# sensorboard_14_v7.net
KiCad netlist of a schematic drawn in EAGLE
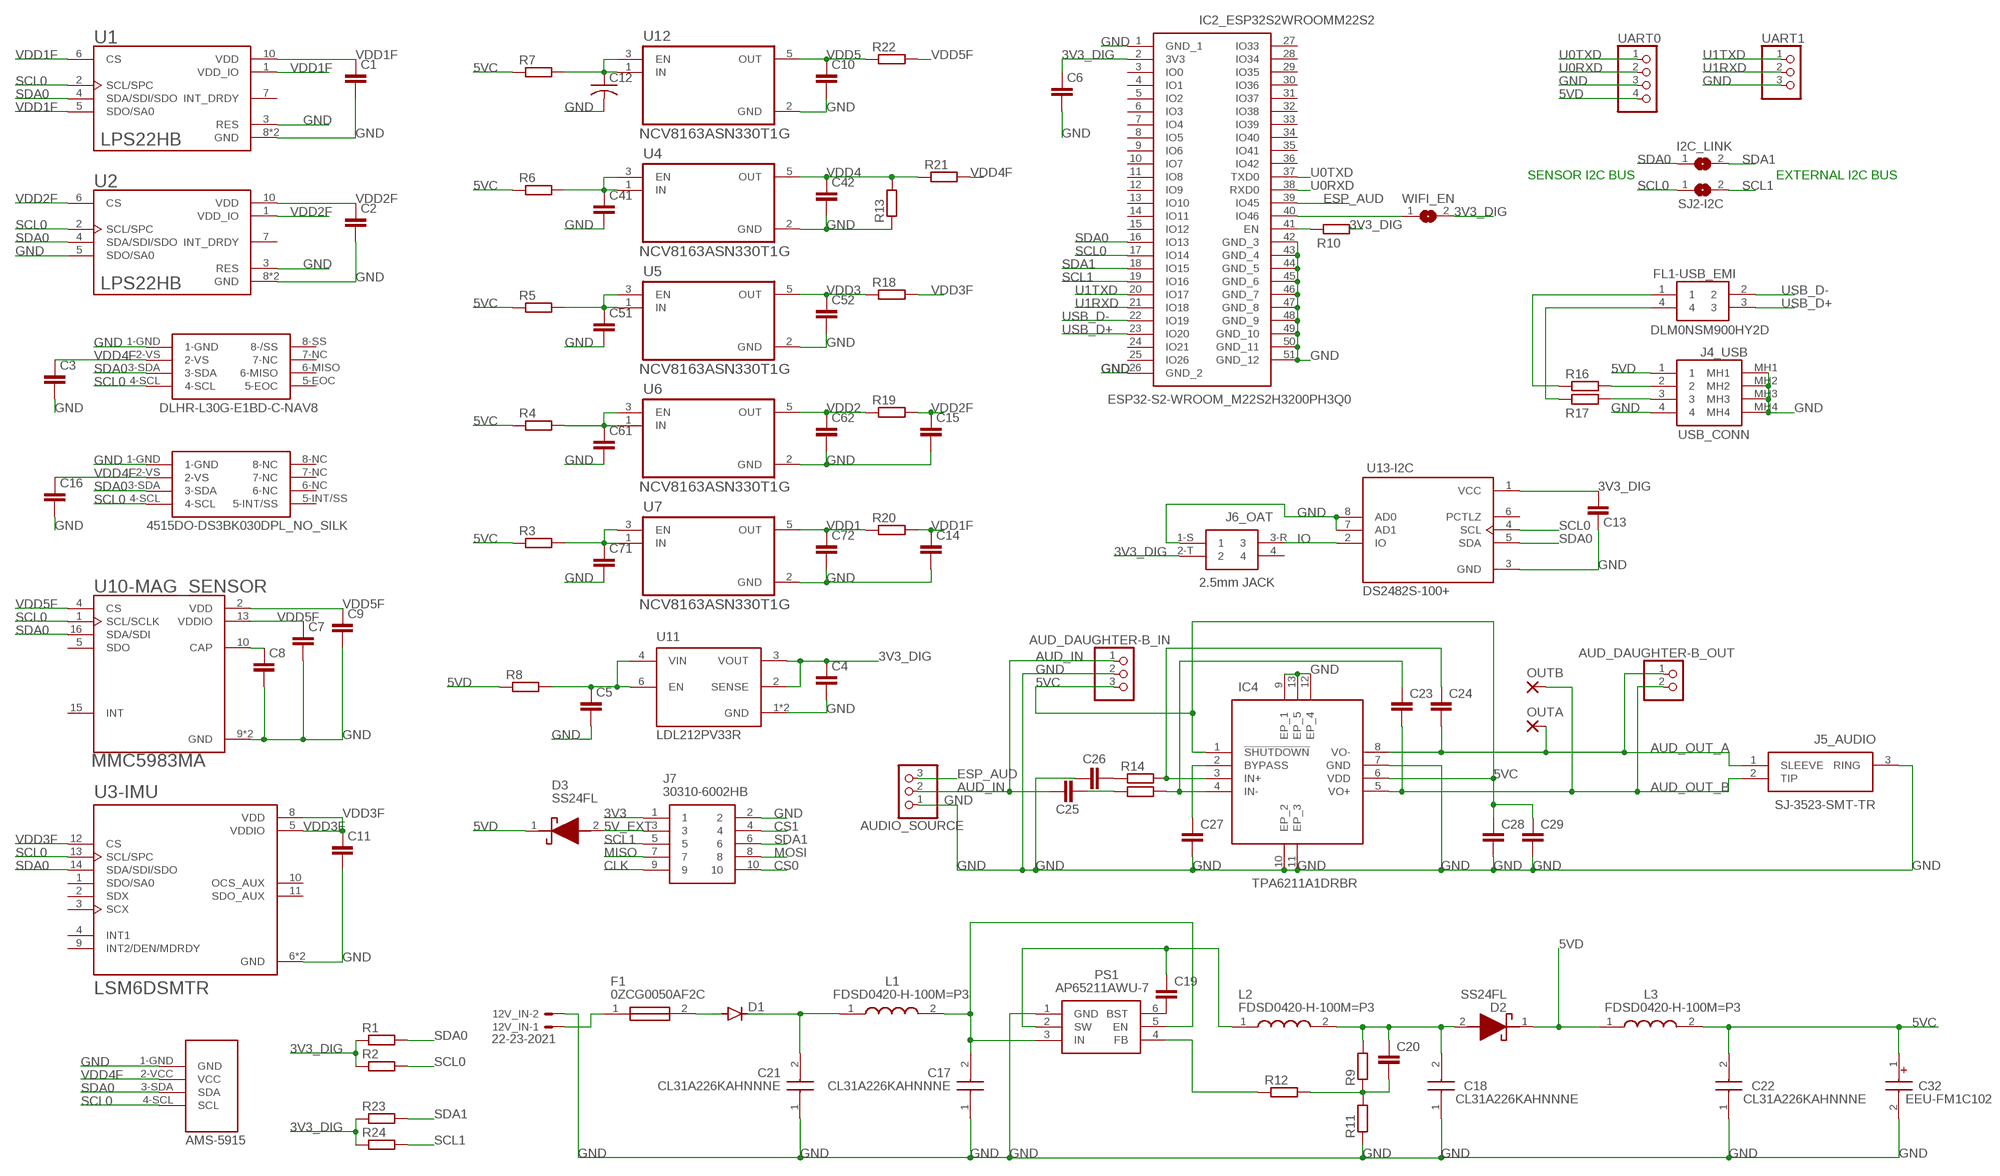
[diagram p0: schematic, sheet 1]

(export (version "E")
  (design (tool "Eeschema 10.0.6"))
  (components
    (comp (ref "12V_IN")
      (value "22-23-2021")
      (footprint "eagle-import:22-23-2021")
      (fields (field (name "MF") "MOLEX"))
      (libsource (lib "eagle-import") (part "22-23-2021"))
    )
    (comp (ref "AUDIO_SOURCE")
      (value "PINHD-1X3")
      (footprint "eagle-import:1X03")
      (libsource (lib "eagle-import") (part "PINHD-1X3"))
    )
    (comp (ref "AUD_DAUGHTER-B_IN")
      (value "PINHD-1X3")
      (footprint "eagle-import:1X03")
      (libsource (lib "eagle-import") (part "PINHD-1X3"))
    )
    (comp (ref "AUD_DAUGHTER-B_OUT")
      (value "PINHD-1X2")
      (footprint "eagle-import:1X02")
      (libsource (lib "eagle-import") (part "PINHD-1X2"))
    )
    (comp (ref "C1")
      (value "C-EUC0603")
      (footprint "eagle-import:C0603")
      (libsource (lib "eagle-import") (part "C-EUC0603"))
    )
    (comp (ref "C2")
      (value "C-EUC0603")
      (footprint "eagle-import:C0603")
      (libsource (lib "eagle-import") (part "C-EUC0603"))
    )
    (comp (ref "C3")
      (value "C-EUC0805")
      (footprint "eagle-import:C0805")
      (libsource (lib "eagle-import") (part "C-EUC0805"))
    )
    (comp (ref "C4")
      (value "C-EUC0805")
      (footprint "eagle-import:C0805")
      (libsource (lib "eagle-import") (part "C-EUC0805"))
    )
    (comp (ref "C5")
      (value "C-EUC0805")
      (footprint "eagle-import:C0805")
      (libsource (lib "eagle-import") (part "C-EUC0805"))
    )
    (comp (ref "C6")
      (value "C-EUC0805")
      (footprint "eagle-import:C0805")
      (libsource (lib "eagle-import") (part "C-EUC0805"))
    )
    (comp (ref "C7")
      (value "C-EUC0805")
      (footprint "eagle-import:C0805")
      (libsource (lib "eagle-import") (part "C-EUC0805"))
    )
    (comp (ref "C8")
      (value "C-EUC0805")
      (footprint "eagle-import:C0805")
      (libsource (lib "eagle-import") (part "C-EUC0805"))
    )
    (comp (ref "C9")
      (value "C-EUC0805")
      (footprint "eagle-import:C0805")
      (libsource (lib "eagle-import") (part "C-EUC0805"))
    )
    (comp (ref "C10")
      (value "C-EUC0805")
      (footprint "eagle-import:C0805")
      (libsource (lib "eagle-import") (part "C-EUC0805"))
    )
    (comp (ref "C11")
      (value "C-EUC0805")
      (footprint "eagle-import:C0805")
      (libsource (lib "eagle-import") (part "C-EUC0805"))
    )
    (comp (ref "C12")
      (value "C-USC0805")
      (footprint "eagle-import:C0805")
      (libsource (lib "eagle-import") (part "C-USC0805"))
    )
    (comp (ref "C13")
      (value "C-EUC0805")
      (footprint "eagle-import:C0805")
      (libsource (lib "eagle-import") (part "C-EUC0805"))
    )
    (comp (ref "C14")
      (value "C-EUC0805")
      (footprint "eagle-import:C0805")
      (libsource (lib "eagle-import") (part "C-EUC0805"))
    )
    (comp (ref "C15")
      (value "C-EUC0805")
      (footprint "eagle-import:C0805")
      (libsource (lib "eagle-import") (part "C-EUC0805"))
    )
    (comp (ref "C16")
      (value "C-EUC0805")
      (footprint "eagle-import:C0805")
      (libsource (lib "eagle-import") (part "C-EUC0805"))
    )
    (comp (ref "C17")
      (value "CL31A226KAHNNNE")
      (footprint "eagle-import:CAPC3216X180N")
      (libsource (lib "eagle-import") (part "CL31A226KAHNNNE"))
    )
    (comp (ref "C18")
      (value "CL31A226KAHNNNE")
      (footprint "eagle-import:CAPC3216X180N")
      (libsource (lib "eagle-import") (part "CL31A226KAHNNNE"))
    )
    (comp (ref "C19")
      (value "C-EUC0805")
      (footprint "eagle-import:C0805")
      (libsource (lib "eagle-import") (part "C-EUC0805"))
    )
    (comp (ref "C20")
      (value "C-EUC0805")
      (footprint "eagle-import:C0805")
      (libsource (lib "eagle-import") (part "C-EUC0805"))
    )
    (comp (ref "C21")
      (value "CL31A226KAHNNNE")
      (footprint "eagle-import:CAPC3216X180N")
      (libsource (lib "eagle-import") (part "CL31A226KAHNNNE"))
    )
    (comp (ref "C22")
      (value "CL31A226KAHNNNE")
      (footprint "eagle-import:CAPC3216X180N")
      (libsource (lib "eagle-import") (part "CL31A226KAHNNNE"))
    )
    (comp (ref "C23")
      (value "C-EUC0805")
      (footprint "eagle-import:C0805")
      (libsource (lib "eagle-import") (part "C-EUC0805"))
    )
    (comp (ref "C24")
      (value "C-EUC0805")
      (footprint "eagle-import:C0805")
      (libsource (lib "eagle-import") (part "C-EUC0805"))
    )
    (comp (ref "C25")
      (value "C-EUC1206")
      (footprint "eagle-import:C1206")
      (libsource (lib "eagle-import") (part "C-EUC1206"))
    )
    (comp (ref "C26")
      (value "C-EUC1206")
      (footprint "eagle-import:C1206")
      (libsource (lib "eagle-import") (part "C-EUC1206"))
    )
    (comp (ref "C27")
      (value "C-EUC1206")
      (footprint "eagle-import:C1206")
      (libsource (lib "eagle-import") (part "C-EUC1206"))
    )
    (comp (ref "C28")
      (value "C-EUC1206")
      (footprint "eagle-import:C1206")
      (libsource (lib "eagle-import") (part "C-EUC1206"))
    )
    (comp (ref "C29")
      (value "C-EUC1206")
      (footprint "eagle-import:C1206")
      (libsource (lib "eagle-import") (part "C-EUC1206"))
    )
    (comp (ref "C32")
      (value "EEU-FM1C102")
      (footprint "eagle-import:CAPPRD500W65D1000H2200")
      (fields (field (name "MOUSER_PART_NUMBER") "667-EEU-FM1C102"))
      (libsource (lib "eagle-import") (part "EEU-FM1C102"))
    )
    (comp (ref "C41")
      (value "C-EUC0805")
      (footprint "eagle-import:C0805")
      (libsource (lib "eagle-import") (part "C-EUC0805"))
    )
    (comp (ref "C42")
      (value "C-EUC0805")
      (footprint "eagle-import:C0805")
      (libsource (lib "eagle-import") (part "C-EUC0805"))
    )
    (comp (ref "C51")
      (value "C-EUC0805")
      (footprint "eagle-import:C0805")
      (libsource (lib "eagle-import") (part "C-EUC0805"))
    )
    (comp (ref "C52")
      (value "C-EUC0805")
      (footprint "eagle-import:C0805")
      (libsource (lib "eagle-import") (part "C-EUC0805"))
    )
    (comp (ref "C61")
      (value "C-EUC0805")
      (footprint "eagle-import:C0805")
      (libsource (lib "eagle-import") (part "C-EUC0805"))
    )
    (comp (ref "C62")
      (value "C-EUC0805")
      (footprint "eagle-import:C0805")
      (libsource (lib "eagle-import") (part "C-EUC0805"))
    )
    (comp (ref "C71")
      (value "C-EUC0805")
      (footprint "eagle-import:C0805")
      (libsource (lib "eagle-import") (part "C-EUC0805"))
    )
    (comp (ref "C72")
      (value "C-EUC0805")
      (footprint "eagle-import:C0805")
      (libsource (lib "eagle-import") (part "C-EUC0805"))
    )
    (comp (ref "D1")
      (value "DIODE-DO-214AC")
      (footprint "eagle-import:DO-214AC")
      (libsource (lib "eagle-import") (part "DIODE-DO-214AC"))
    )
    (comp (ref "D2")
      (value "SS24FL")
      (footprint "eagle-import:SODFL3617X108N")
      (fields (field (name "MOUSER_PART_NUMBER") "512-SS24FL"))
      (libsource (lib "eagle-import") (part "SS24FL"))
    )
    (comp (ref "D3")
      (value "SS24FL")
      (footprint "eagle-import:SODFL3617X108N")
      (fields (field (name "MOUSER_PART_NUMBER") "512-SS24FL"))
      (libsource (lib "eagle-import") (part "SS24FL"))
    )
    (comp (ref "DLHR-L30G-E1BD-C-NAV8")
      (value "DLHR-L30G-E1BD-C-NAV8")
      (footprint "eagle-import:DLHR-L30G-E1BD-C-NAV8")
      (libsource (lib "eagle-import") (part "DLHR-L30G-E1BD-C-NAV8"))
    )
    (comp (ref "F1")
      (value "0ZCG0050AF2C")
      (footprint "eagle-import:FUSC4632X75N")
      (fields (field (name "MOUSER_PART_NUMBER") "530-0ZCG0050AF2C"))
      (libsource (lib "eagle-import") (part "0ZCG0050AF2C"))
    )
    (comp (ref "FL1-USB_EMI")
      (value "DLM0NSM900HY2D")
      (footprint "eagle-import:DLM0NSB120HY2B")
      (fields (field (name "MOUSER_PART_NUMBER") "81-DLM0NSM900HY2D"))
      (libsource (lib "eagle-import") (part "DLM0NSM900HY2D"))
    )
    (comp (ref "I2C_LINK")
      (value "SJ")
      (footprint "eagle-import:SJ")
      (libsource (lib "eagle-import") (part "SJ"))
    )
    (comp (ref "IC2_ESP32S2WROOMM22S2")
      (value "ESP32-S2-WROOM_M22S2H3200PH3Q0")
      (footprint "eagle-import:ESP32S2WROOMM22S2H3200PH3Q0")
      (fields
        (field (name "MANUFACTURER_PART_NUMBER") "ESP32-S2-WROOM(M22S2H3200PH3Q0)")
        (field (name "MOUSER_PART_NUMBER") "356-ESP32S2WRM3200PH")
      )
      (libsource (lib "eagle-import") (part "ESP32-S2-WROOM_M22S2H3200PH3Q0"))
    )
    (comp (ref "IC4")
      (value "TPA6211A1DRBR")
      (footprint "eagle-import:TPS7A8033DRBT")
      (fields (field (name "MOUSER_PART_NUMBER") "595-TPA6211A1DRBR"))
      (libsource (lib "eagle-import") (part "TPA6211A1DRBR"))
    )
    (comp (ref "J4_USB")
      (value "USB_CONN")
      (footprint "eagle-import:737250110BLF")
      (fields
        (field (name "MANUFACTURER_PART_NUMBER") "73725-0110BLF")
        (field (name "MOUSER_PART_NUMBER") "649-73725-0110BLF")
      )
      (libsource (lib "eagle-import") (part "73725-0110BLF"))
    )
    (comp (ref "J5_AUDIO")
      (value "SJ-3523-SMT-TR")
      (footprint "eagle-import:SJ3523SMTTR")
      (fields (field (name "MOUSER_PART_NUMBER") "490-SJ-3523-SMT-TR"))
      (libsource (lib "eagle-import") (part "SJ-3523-SMT-TR"))
    )
    (comp (ref "J6_OAT")
      (value "2.5mm JACK")
      (footprint "eagle-import:SJ-2523-SMT-TR")
      (fields
        (field (name "MANUFACTURER_PART_NUMBER") "SJ-2523-SMT-TR")
        (field (name "MOUSER_PART_NUMBER") "490-SJ-2523-SMT-TR")
      )
      (libsource (lib "eagle-import") (part "SJ-2523-SMT-TR"))
    )
    (comp (ref "J7")
      (value "30310-6002HB")
      (footprint "eagle-import:SHDR10W64P254_2X5_2030X878X930")
      (fields (field (name "MOUSER_PART_NUMBER") "517-30310-6002"))
      (libsource (lib "eagle-import") (part "30310-6002HB"))
    )
    (comp (ref "L1")
      (value "FDSD0420-H-100M=P3")
      (footprint "eagle-import:FDSD0420WH150MP3")
      (fields (field (name "MOUSER_PART_NUMBER") "81-FDSD0420-H-100MP3"))
      (libsource (lib "eagle-import") (part "FDSD0420-H-100M=P3"))
    )
    (comp (ref "L2")
      (value "FDSD0420-H-100M=P3")
      (footprint "eagle-import:FDSD0420WH150MP3")
      (fields (field (name "MOUSER_PART_NUMBER") "81-FDSD0420-H-100MP3"))
      (libsource (lib "eagle-import") (part "FDSD0420-H-100M=P3"))
    )
    (comp (ref "L3")
      (value "FDSD0420-H-100M=P3")
      (footprint "eagle-import:FDSD0420WH150MP3")
      (fields (field (name "MOUSER_PART_NUMBER") "81-FDSD0420-H-100MP3"))
      (libsource (lib "eagle-import") (part "FDSD0420-H-100M=P3"))
    )
    (comp (ref "OUTA")
      (value "SMD2_SMALLSMALL")
      (footprint "eagle-import:SMD2_SMALL")
      (libsource (lib "eagle-import") (part "SMD2_SMALLSMALL"))
    )
    (comp (ref "OUTB")
      (value "SMD2_SMALLSMALL")
      (footprint "eagle-import:SMD2_SMALL")
      (libsource (lib "eagle-import") (part "SMD2_SMALLSMALL"))
    )
    (comp (ref "PS1")
      (value "AP65211AWU-7")
      (footprint "eagle-import:SOT95P280X90-6N")
      (fields (field (name "MOUSER_PART_NUMBER") "621-AP65211AWU-7"))
      (libsource (lib "eagle-import") (part "AP65211AWU-7"))
    )
    (comp (ref "R1")
      (value "R-EU_R0805")
      (footprint "eagle-import:R0805")
      (libsource (lib "eagle-import") (part "R-EU_R0805"))
    )
    (comp (ref "R2")
      (value "R-EU_R0805")
      (footprint "eagle-import:R0805")
      (libsource (lib "eagle-import") (part "R-EU_R0805"))
    )
    (comp (ref "R3")
      (value "R-EU_R0805")
      (footprint "eagle-import:R0805")
      (libsource (lib "eagle-import") (part "R-EU_R0805"))
    )
    (comp (ref "R4")
      (value "R-EU_R0805")
      (footprint "eagle-import:R0805")
      (libsource (lib "eagle-import") (part "R-EU_R0805"))
    )
    (comp (ref "R5")
      (value "R-EU_R0805")
      (footprint "eagle-import:R0805")
      (libsource (lib "eagle-import") (part "R-EU_R0805"))
    )
    (comp (ref "R6")
      (value "R-EU_R0805")
      (footprint "eagle-import:R0805")
      (libsource (lib "eagle-import") (part "R-EU_R0805"))
    )
    (comp (ref "R7")
      (value "R-EU_R0805")
      (footprint "eagle-import:R0805")
      (libsource (lib "eagle-import") (part "R-EU_R0805"))
    )
    (comp (ref "R8")
      (value "R-EU_R0805")
      (footprint "eagle-import:R0805")
      (libsource (lib "eagle-import") (part "R-EU_R0805"))
    )
    (comp (ref "R9")
      (value "R-EU_R0805")
      (footprint "eagle-import:R0805")
      (libsource (lib "eagle-import") (part "R-EU_R0805"))
    )
    (comp (ref "R10")
      (value "R-EU_R0805")
      (footprint "eagle-import:R0805")
      (libsource (lib "eagle-import") (part "R-EU_R0805"))
    )
    (comp (ref "R11")
      (value "R-EU_R0805")
      (footprint "eagle-import:R0805")
      (libsource (lib "eagle-import") (part "R-EU_R0805"))
    )
    (comp (ref "R12")
      (value "R-EU_R0805")
      (footprint "eagle-import:R0805")
      (libsource (lib "eagle-import") (part "R-EU_R0805"))
    )
    (comp (ref "R13")
      (value "R-EU_R0805")
      (footprint "eagle-import:R0805")
      (libsource (lib "eagle-import") (part "R-EU_R0805"))
    )
    (comp (ref "R14")
      (value "R-EU_R0805")
      (footprint "eagle-import:R0805")
      (libsource (lib "eagle-import") (part "R-EU_R0805"))
    )
    (comp (ref "R15")
      (value "R-EU_R0805")
      (footprint "eagle-import:R0805")
      (libsource (lib "eagle-import") (part "R-EU_R0805"))
    )
    (comp (ref "R16")
      (value "R-EU_R0805")
      (footprint "eagle-import:R0805")
      (libsource (lib "eagle-import") (part "R-EU_R0805"))
    )
    (comp (ref "R17")
      (value "R-EU_R0805")
      (footprint "eagle-import:R0805")
      (libsource (lib "eagle-import") (part "R-EU_R0805"))
    )
    (comp (ref "R18")
      (value "R-EU_R0805")
      (footprint "eagle-import:R0805")
      (libsource (lib "eagle-import") (part "R-EU_R0805"))
    )
    (comp (ref "R19")
      (value "R-EU_R0805")
      (footprint "eagle-import:R0805")
      (libsource (lib "eagle-import") (part "R-EU_R0805"))
    )
    (comp (ref "R20")
      (value "R-EU_R0805")
      (footprint "eagle-import:R0805")
      (libsource (lib "eagle-import") (part "R-EU_R0805"))
    )
    (comp (ref "R21")
      (value "R-EU_R0805")
      (footprint "eagle-import:R0805")
      (libsource (lib "eagle-import") (part "R-EU_R0805"))
    )
    (comp (ref "R22")
      (value "R-EU_R0805")
      (footprint "eagle-import:R0805")
      (libsource (lib "eagle-import") (part "R-EU_R0805"))
    )
    (comp (ref "R23")
      (value "R-EU_R0805")
      (footprint "eagle-import:R0805")
      (libsource (lib "eagle-import") (part "R-EU_R0805"))
    )
    (comp (ref "R24")
      (value "R-EU_R0805")
      (footprint "eagle-import:R0805")
      (libsource (lib "eagle-import") (part "R-EU_R0805"))
    )
    (comp (ref "SJ2-I2C")
      (value "SJ")
      (footprint "eagle-import:SJ")
      (libsource (lib "eagle-import") (part "SJ"))
    )
    (comp (ref "U$1")
      (value "AMS-5915")
      (footprint "eagle-import:AMS-5915")
      (libsource (lib "eagle-import") (part "AMS-5915"))
    )
    (comp (ref "U$4")
      (value "4515DO-DS3BK030DPL_NO_SILKNO_SILK")
      (footprint "eagle-import:4515DO-DS3BK030DPL_NO_SILK")
      (libsource (lib "eagle-import") (part "4515DO-DS3BK030DPL_NO_SILKNO_SILK"))
    )
    (comp (ref "U1")
      (value "LPS22HB")
      (footprint "eagle-import:LGA10R50P2X3_200X200X80")
      (fields (field (name "MF") "STMicroelectronics"))
      (libsource (lib "eagle-import") (part "LPS22HB"))
    )
    (comp (ref "U2")
      (value "LPS22HB")
      (footprint "eagle-import:LGA10R50P2X3_200X200X80")
      (fields (field (name "MF") "STMicroelectronics"))
      (libsource (lib "eagle-import") (part "LPS22HB"))
    )
    (comp (ref "U3-IMU")
      (value "LSM6DSMTR")
      (footprint "eagle-import:PQFN50P300X250X86-14N")
      (fields (field (name "MF") "STMicroelectronics"))
      (libsource (lib "eagle-import") (part "LSM6DSMTR"))
    )
    (comp (ref "U4")
      (value "NCV8163ASN330T1G")
      (footprint "eagle-import:SOP95P275X110-5N")
      (fields (field (name "MF") "ON Semiconductor"))
      (libsource (lib "eagle-import") (part "NCV8163ASN330T1G"))
    )
    (comp (ref "U5")
      (value "NCV8163ASN330T1G")
      (footprint "eagle-import:SOP95P275X110-5N")
      (fields (field (name "MF") "ON Semiconductor"))
      (libsource (lib "eagle-import") (part "NCV8163ASN330T1G"))
    )
    (comp (ref "U6")
      (value "NCV8163ASN330T1G")
      (footprint "eagle-import:SOP95P275X110-5N")
      (fields (field (name "MF") "ON Semiconductor"))
      (libsource (lib "eagle-import") (part "NCV8163ASN330T1G"))
    )
    (comp (ref "U7")
      (value "NCV8163ASN330T1G")
      (footprint "eagle-import:SOP95P275X110-5N")
      (fields (field (name "MF") "ON Semiconductor"))
      (libsource (lib "eagle-import") (part "NCV8163ASN330T1G"))
    )
    (comp (ref "U10-MAG_SENSOR")
      (value "MMC5983MA")
      (footprint "eagle-import:LGA16R50P4X4_330X330X100")
      (fields (field (name "MF") "ON Semiconductor") (field (name "MP") "FIS1100"))
      (libsource (lib "eagle-import") (part "MMC5983MA"))
    )
    (comp (ref "U11")
      (value "LDL212PV33R")
      (footprint "eagle-import:SON50P200X200X80-7N")
      (fields (field (name "MF") "STMicroelectronics"))
      (libsource (lib "eagle-import") (part "LDL212PV33R"))
    )
    (comp (ref "U12")
      (value "NCV8163ASN330T1G")
      (footprint "eagle-import:SOP95P275X110-5N")
      (fields (field (name "MF") "ON Semiconductor"))
      (libsource (lib "eagle-import") (part "NCV8163ASN330T1G"))
    )
    (comp (ref "U13-I2C")
      (value "DS2482S-100+")
      (footprint "eagle-import:SOIC127P600X175-8N")
      (fields (field (name "MF") "Maxim Integrated"))
      (libsource (lib "eagle-import") (part "DS2482S-100+"))
    )
    (comp (ref "UART0")
      (value "PINHD-1X4")
      (footprint "eagle-import:1X04")
      (libsource (lib "eagle-import") (part "PINHD-1X4"))
    )
    (comp (ref "UART1")
      (value "PINHD-1X3")
      (footprint "eagle-import:1X03")
      (libsource (lib "eagle-import") (part "PINHD-1X3"))
    )
    (comp (ref "WIFI_EN")
      (value "SJ")
      (footprint "eagle-import:SJ")
      (libsource (lib "eagle-import") (part "SJ"))
    )
  )
  (nets
    (net (code "1") (name "/3V3") (class "Default")
      (node (ref "J7") (pin "1") (pinfunction "1_1") (pintype "bidirectional"))
    )
    (net (code "2") (name "/3V3_DIG") (class "Default")
      (node (ref "C13") (pin "1") (pinfunction "1_1") (pintype "passive"))
      (node (ref "C4") (pin "1") (pinfunction "1_1") (pintype "passive"))
      (node (ref "C6") (pin "1") (pinfunction "1_1") (pintype "passive"))
      (node (ref "IC2_ESP32S2WROOMM22S2") (pin "2") (pinfunction "3V3_2") (pintype "bidirectional"))
      (node (ref "J6_OAT") (pin "2-T") (pinfunction "2_2-T") (pintype "bidirectional"))
      (node (ref "R1") (pin "1") (pinfunction "1_1") (pintype "passive"))
      (node (ref "R10") (pin "2") (pinfunction "2_2") (pintype "passive"))
      (node (ref "R2") (pin "1") (pinfunction "1_1") (pintype "passive"))
      (node (ref "R23") (pin "1") (pinfunction "1_1") (pintype "passive"))
      (node (ref "R24") (pin "1") (pinfunction "1_1") (pintype "passive"))
      (node (ref "U11") (pin "2") (pinfunction "SENSE_2") (pintype "input"))
      (node (ref "U11") (pin "3") (pinfunction "VOUT_3") (pintype "output"))
      (node (ref "U13-I2C") (pin "1") (pinfunction "VCC_1") (pintype "power_in"))
      (node (ref "WIFI_EN") (pin "2") (pinfunction "2_2") (pintype "passive"))
    )
    (net (code "3") (name "/5VC") (class "Default")
      (node (ref "AUD_DAUGHTER-B_IN") (pin "3") (pinfunction "3_3") (pintype "passive"))
      (node (ref "C22") (pin "2") (pinfunction "2_2") (pintype "bidirectional"))
      (node (ref "C28") (pin "1") (pinfunction "1_1") (pintype "passive"))
      (node (ref "C29") (pin "1") (pinfunction "1_1") (pintype "passive"))
      (node (ref "C32") (pin "1") (pinfunction "+_1") (pintype "bidirectional"))
      (node (ref "IC4") (pin "1") (pinfunction "~{SHUTDOWN}_1") (pintype "bidirectional"))
      (node (ref "IC4") (pin "6") (pinfunction "VDD_6") (pintype "bidirectional"))
      (node (ref "L3") (pin "2") (pinfunction "2_2") (pintype "bidirectional"))
      (node (ref "R3") (pin "1") (pinfunction "1_1") (pintype "passive"))
      (node (ref "R4") (pin "1") (pinfunction "1_1") (pintype "passive"))
      (node (ref "R5") (pin "1") (pinfunction "1_1") (pintype "passive"))
      (node (ref "R6") (pin "1") (pinfunction "1_1") (pintype "passive"))
      (node (ref "R7") (pin "1") (pinfunction "1_1") (pintype "passive"))
    )
    (net (code "4") (name "/5VD") (class "Default")
      (node (ref "D2") (pin "1") (pinfunction "K_1") (pintype "bidirectional"))
      (node (ref "D3") (pin "1") (pinfunction "K_1") (pintype "bidirectional"))
      (node (ref "J4_USB") (pin "1") (pinfunction "1_1") (pintype "bidirectional"))
      (node (ref "L3") (pin "1") (pinfunction "1_1") (pintype "bidirectional"))
      (node (ref "R8") (pin "1") (pinfunction "1_1") (pintype "passive"))
      (node (ref "UART0") (pin "4") (pinfunction "4_4") (pintype "passive"))
    )
    (net (code "5") (name "/5V_EXT") (class "Default")
      (node (ref "D3") (pin "2") (pinfunction "A_2") (pintype "bidirectional"))
      (node (ref "J7") (pin "3") (pinfunction "3_3") (pintype "bidirectional"))
    )
    (net (code "6") (name "/AUD_IN") (class "Default")
      (node (ref "AUDIO_SOURCE") (pin "2") (pinfunction "2_2") (pintype "passive"))
      (node (ref "AUD_DAUGHTER-B_IN") (pin "1") (pinfunction "1_1") (pintype "passive"))
      (node (ref "C25") (pin "1") (pinfunction "1_1") (pintype "passive"))
    )
    (net (code "7") (name "/AUD_OUT_A") (class "Default")
      (node (ref "AUD_DAUGHTER-B_OUT") (pin "1") (pinfunction "1_1") (pintype "passive"))
      (node (ref "C24") (pin "2") (pinfunction "2_2") (pintype "passive"))
      (node (ref "IC4") (pin "8") (pinfunction "VO-_8") (pintype "bidirectional"))
      (node (ref "J5_AUDIO") (pin "1") (pinfunction "SLEEVE_1") (pintype "bidirectional"))
      (node (ref "OUTA") (pin "1") (pinfunction "P_1") (pintype "passive"))
    )
    (net (code "8") (name "/AUD_OUT_B") (class "Default")
      (node (ref "AUD_DAUGHTER-B_OUT") (pin "2") (pinfunction "2_2") (pintype "passive"))
      (node (ref "C23") (pin "2") (pinfunction "2_2") (pintype "passive"))
      (node (ref "IC4") (pin "5") (pinfunction "VO+_5") (pintype "bidirectional"))
      (node (ref "J5_AUDIO") (pin "2") (pinfunction "TIP_2") (pintype "bidirectional"))
      (node (ref "OUTB") (pin "1") (pinfunction "P_1") (pintype "passive"))
    )
    (net (code "9") (name "/CLK") (class "Default")
      (node (ref "J7") (pin "9") (pinfunction "9_9") (pintype "bidirectional"))
    )
    (net (code "10") (name "/CS0") (class "Default")
      (node (ref "J7") (pin "10") (pinfunction "10_10") (pintype "bidirectional"))
    )
    (net (code "11") (name "/CS1") (class "Default")
      (node (ref "J7") (pin "4") (pinfunction "4_4") (pintype "bidirectional"))
    )
    (net (code "12") (name "/ESP_AUD") (class "Default")
      (node (ref "AUDIO_SOURCE") (pin "3") (pinfunction "3_3") (pintype "passive"))
      (node (ref "IC2_ESP32S2WROOMM22S2") (pin "39") (pinfunction "IO45_39") (pintype "bidirectional"))
    )
    (net (code "13") (name "/GND") (class "Default")
      (node (ref "12V_IN") (pin "2") (pinfunction "S_2") (pintype "passive"))
      (node (ref "AUDIO_SOURCE") (pin "1") (pinfunction "1_1") (pintype "passive"))
      (node (ref "AUD_DAUGHTER-B_IN") (pin "2") (pinfunction "2_2") (pintype "passive"))
      (node (ref "C1") (pin "2") (pinfunction "2_2") (pintype "passive"))
      (node (ref "C10") (pin "2") (pinfunction "2_2") (pintype "passive"))
      (node (ref "C11") (pin "2") (pinfunction "2_2") (pintype "passive"))
      (node (ref "C12") (pin "2") (pinfunction "2_2") (pintype "passive"))
      (node (ref "C13") (pin "2") (pinfunction "2_2") (pintype "passive"))
      (node (ref "C14") (pin "2") (pinfunction "2_2") (pintype "passive"))
      (node (ref "C15") (pin "2") (pinfunction "2_2") (pintype "passive"))
      (node (ref "C16") (pin "2") (pinfunction "2_2") (pintype "passive"))
      (node (ref "C17") (pin "1") (pinfunction "1_1") (pintype "bidirectional"))
      (node (ref "C18") (pin "1") (pinfunction "1_1") (pintype "bidirectional"))
      (node (ref "C2") (pin "2") (pinfunction "2_2") (pintype "passive"))
      (node (ref "C21") (pin "1") (pinfunction "1_1") (pintype "bidirectional"))
      (node (ref "C22") (pin "1") (pinfunction "1_1") (pintype "bidirectional"))
      (node (ref "C26") (pin "1") (pinfunction "1_1") (pintype "passive"))
      (node (ref "C27") (pin "2") (pinfunction "2_2") (pintype "passive"))
      (node (ref "C28") (pin "2") (pinfunction "2_2") (pintype "passive"))
      (node (ref "C29") (pin "2") (pinfunction "2_2") (pintype "passive"))
      (node (ref "C3") (pin "2") (pinfunction "2_2") (pintype "passive"))
      (node (ref "C32") (pin "2") (pinfunction "-_2") (pintype "bidirectional"))
      (node (ref "C4") (pin "2") (pinfunction "2_2") (pintype "passive"))
      (node (ref "C41") (pin "2") (pinfunction "2_2") (pintype "passive"))
      (node (ref "C42") (pin "2") (pinfunction "2_2") (pintype "passive"))
      (node (ref "C5") (pin "2") (pinfunction "2_2") (pintype "passive"))
      (node (ref "C51") (pin "2") (pinfunction "2_2") (pintype "passive"))
      (node (ref "C52") (pin "2") (pinfunction "2_2") (pintype "passive"))
      (node (ref "C6") (pin "2") (pinfunction "2_2") (pintype "passive"))
      (node (ref "C61") (pin "2") (pinfunction "2_2") (pintype "passive"))
      (node (ref "C62") (pin "2") (pinfunction "2_2") (pintype "passive"))
      (node (ref "C7") (pin "2") (pinfunction "2_2") (pintype "passive"))
      (node (ref "C71") (pin "2") (pinfunction "2_2") (pintype "passive"))
      (node (ref "C72") (pin "2") (pinfunction "2_2") (pintype "passive"))
      (node (ref "C8") (pin "2") (pinfunction "2_2") (pintype "passive"))
      (node (ref "C9") (pin "2") (pinfunction "2_2") (pintype "passive"))
      (node (ref "DLHR-L30G-E1BD-C-NAV8") (pin "1-GND") (pinfunction "1-GND_1-GND") (pintype "power_in"))
      (node (ref "IC2_ESP32S2WROOMM22S2") (pin "1") (pinfunction "GND_1_1") (pintype "bidirectional"))
      (node (ref "IC2_ESP32S2WROOMM22S2") (pin "26") (pinfunction "GND_2_26") (pintype "bidirectional"))
      (node (ref "IC2_ESP32S2WROOMM22S2") (pin "42") (pinfunction "GND_3_42") (pintype "bidirectional"))
      (node (ref "IC2_ESP32S2WROOMM22S2") (pin "43") (pinfunction "GND_4_43") (pintype "bidirectional"))
      (node (ref "IC2_ESP32S2WROOMM22S2") (pin "44") (pinfunction "GND_5_44") (pintype "bidirectional"))
      (node (ref "IC2_ESP32S2WROOMM22S2") (pin "45") (pinfunction "GND_6_45") (pintype "bidirectional"))
      (node (ref "IC2_ESP32S2WROOMM22S2") (pin "46") (pinfunction "GND_7_46") (pintype "bidirectional"))
      (node (ref "IC2_ESP32S2WROOMM22S2") (pin "47") (pinfunction "GND_8_47") (pintype "bidirectional"))
      (node (ref "IC2_ESP32S2WROOMM22S2") (pin "48") (pinfunction "GND_9_48") (pintype "bidirectional"))
      (node (ref "IC2_ESP32S2WROOMM22S2") (pin "49") (pinfunction "GND_10_49") (pintype "bidirectional"))
      (node (ref "IC2_ESP32S2WROOMM22S2") (pin "50") (pinfunction "GND_11_50") (pintype "bidirectional"))
      (node (ref "IC2_ESP32S2WROOMM22S2") (pin "51") (pinfunction "GND_12_51") (pintype "bidirectional"))
      (node (ref "IC4") (pin "10") (pinfunction "EP_2_10") (pintype "bidirectional"))
      (node (ref "IC4") (pin "11") (pinfunction "EP_3_11") (pintype "bidirectional"))
      (node (ref "IC4") (pin "12") (pinfunction "EP_4_12") (pintype "bidirectional"))
      (node (ref "IC4") (pin "13") (pinfunction "EP_5_13") (pintype "bidirectional"))
      (node (ref "IC4") (pin "7") (pinfunction "GND_7") (pintype "bidirectional"))
      (node (ref "IC4") (pin "9") (pinfunction "EP_1_9") (pintype "bidirectional"))
      (node (ref "J4_USB") (pin "4") (pinfunction "4_4") (pintype "bidirectional"))
      (node (ref "J4_USB") (pin "MH1") (pinfunction "MH1_MH1") (pintype "bidirectional"))
      (node (ref "J4_USB") (pin "MH2") (pinfunction "MH2_MH2") (pintype "bidirectional"))
      (node (ref "J4_USB") (pin "MH3") (pinfunction "MH3_MH3") (pintype "bidirectional"))
      (node (ref "J4_USB") (pin "MH4") (pinfunction "MH4_MH4") (pintype "bidirectional"))
      (node (ref "J5_AUDIO") (pin "3") (pinfunction "RING_3") (pintype "bidirectional"))
      (node (ref "J6_OAT") (pin "1-S") (pinfunction "1_1-S") (pintype "bidirectional"))
      (node (ref "J7") (pin "2") (pinfunction "2_2") (pintype "bidirectional"))
      (node (ref "PS1") (pin "1") (pinfunction "GND_1") (pintype "power_in"))
      (node (ref "R11") (pin "1") (pinfunction "1_1") (pintype "passive"))
      (node (ref "R13") (pin "1") (pinfunction "1_1") (pintype "passive"))
      (node (ref "U$1") (pin "1-GND") (pinfunction "GND_1-GND") (pintype "bidirectional"))
      (node (ref "U$4") (pin "1-GND") (pinfunction "1-GND_1-GND") (pintype "power_in"))
      (node (ref "U1") (pin "3") (pinfunction "RES_3") (pintype "power_in"))
      (node (ref "U1") (pin "8") (pinfunction "GND_8") (pintype "power_in"))
      (node (ref "U1") (pin "9") (pinfunction "GND_9") (pintype "power_in"))
      (node (ref "U10-MAG_SENSOR") (pin "11") (pinfunction "GND_11") (pintype "power_in"))
      (node (ref "U10-MAG_SENSOR") (pin "9") (pinfunction "GND_9") (pintype "power_in"))
      (node (ref "U11") (pin "1") (pinfunction "GND_1") (pintype "power_in"))
      (node (ref "U11") (pin "7") (pinfunction "GND_7") (pintype "power_in"))
      (node (ref "U12") (pin "2") (pinfunction "GND_2") (pintype "power_in"))
      (node (ref "U13-I2C") (pin "3") (pinfunction "GND_3") (pintype "power_in"))
      (node (ref "U13-I2C") (pin "7") (pinfunction "AD1_7") (pintype "input"))
      (node (ref "U13-I2C") (pin "8") (pinfunction "AD0_8") (pintype "input"))
      (node (ref "U2") (pin "3") (pinfunction "RES_3") (pintype "power_in"))
      (node (ref "U2") (pin "5") (pinfunction "SDO/SA0_5") (pintype "bidirectional"))
      (node (ref "U2") (pin "8") (pinfunction "GND_8") (pintype "power_in"))
      (node (ref "U2") (pin "9") (pinfunction "GND_9") (pintype "power_in"))
      (node (ref "U3-IMU") (pin "6") (pinfunction "GND_6") (pintype "power_in"))
      (node (ref "U3-IMU") (pin "7") (pinfunction "GND_7") (pintype "power_in"))
      (node (ref "U4") (pin "2") (pinfunction "GND_2") (pintype "power_in"))
      (node (ref "U5") (pin "2") (pinfunction "GND_2") (pintype "power_in"))
      (node (ref "U6") (pin "2") (pinfunction "GND_2") (pintype "power_in"))
      (node (ref "U7") (pin "2") (pinfunction "GND_2") (pintype "power_in"))
      (node (ref "UART0") (pin "3") (pinfunction "3_3") (pintype "passive"))
      (node (ref "UART1") (pin "3") (pinfunction "3_3") (pintype "passive"))
    )
    (net (code "14") (name "/IO") (class "Default")
      (node (ref "J6_OAT") (pin "3-R") (pinfunction "3_3-R") (pintype "bidirectional"))
      (node (ref "U13-I2C") (pin "2") (pinfunction "IO_2") (pintype "bidirectional"))
    )
    (net (code "15") (name "/MISO") (class "Default")
      (node (ref "J7") (pin "7") (pinfunction "7_7") (pintype "bidirectional"))
    )
    (net (code "16") (name "/MOSI") (class "Default")
      (node (ref "J7") (pin "8") (pinfunction "8_8") (pintype "bidirectional"))
    )
    (net (code "17") (name "/SCL0") (class "Default")
      (node (ref "DLHR-L30G-E1BD-C-NAV8") (pin "4-SCL") (pinfunction "4-SCL_4-SCL") (pintype "bidirectional"))
      (node (ref "IC2_ESP32S2WROOMM22S2") (pin "17") (pinfunction "IO14_17") (pintype "bidirectional"))
      (node (ref "R2") (pin "2") (pinfunction "2_2") (pintype "passive"))
      (node (ref "SJ2-I2C") (pin "1") (pinfunction "1_1") (pintype "passive"))
      (node (ref "U$1") (pin "4-SCL") (pinfunction "SCL_4-SCL") (pintype "bidirectional"))
      (node (ref "U$4") (pin "4-SCL") (pinfunction "4-SCL_4-SCL") (pintype "bidirectional"))
      (node (ref "U1") (pin "2") (pinfunction "SCL/SPC_2") (pintype "input"))
      (node (ref "U10-MAG_SENSOR") (pin "1") (pinfunction "SCL/SCLK_1") (pintype "bidirectional"))
      (node (ref "U13-I2C") (pin "4") (pinfunction "SCL_4") (pintype "input"))
      (node (ref "U2") (pin "2") (pinfunction "SCL/SPC_2") (pintype "input"))
      (node (ref "U3-IMU") (pin "13") (pinfunction "SCL/SPC_13") (pintype "input"))
    )
    (net (code "18") (name "/SCL1") (class "Default")
      (node (ref "IC2_ESP32S2WROOMM22S2") (pin "19") (pinfunction "IO16_19") (pintype "bidirectional"))
      (node (ref "J7") (pin "5") (pinfunction "5_5") (pintype "bidirectional"))
      (node (ref "R24") (pin "2") (pinfunction "2_2") (pintype "passive"))
      (node (ref "SJ2-I2C") (pin "2") (pinfunction "2_2") (pintype "passive"))
    )
    (net (code "19") (name "/SDA0") (class "Default")
      (node (ref "DLHR-L30G-E1BD-C-NAV8") (pin "3-SDA") (pinfunction "3-SDA_3-SDA") (pintype "bidirectional"))
      (node (ref "I2C_LINK") (pin "1") (pinfunction "1_1") (pintype "passive"))
      (node (ref "IC2_ESP32S2WROOMM22S2") (pin "16") (pinfunction "IO13_16") (pintype "bidirectional"))
      (node (ref "R1") (pin "2") (pinfunction "2_2") (pintype "passive"))
      (node (ref "U$1") (pin "3-SDA") (pinfunction "SDA_3-SDA") (pintype "bidirectional"))
      (node (ref "U$4") (pin "3-SDA") (pinfunction "3-SDA_3-SDA") (pintype "bidirectional"))
      (node (ref "U1") (pin "4") (pinfunction "SDA/SDI/SDO_4") (pintype "bidirectional"))
      (node (ref "U10-MAG_SENSOR") (pin "16") (pinfunction "SDA/SDI_16") (pintype "bidirectional"))
      (node (ref "U13-I2C") (pin "5") (pinfunction "SDA_5") (pintype "bidirectional"))
      (node (ref "U2") (pin "4") (pinfunction "SDA/SDI/SDO_4") (pintype "bidirectional"))
      (node (ref "U3-IMU") (pin "14") (pinfunction "SDA/SDI/SDO_14") (pintype "bidirectional"))
    )
    (net (code "20") (name "/SDA1") (class "Default")
      (node (ref "I2C_LINK") (pin "2") (pinfunction "2_2") (pintype "passive"))
      (node (ref "IC2_ESP32S2WROOMM22S2") (pin "18") (pinfunction "IO15_18") (pintype "bidirectional"))
      (node (ref "J7") (pin "6") (pinfunction "6_6") (pintype "bidirectional"))
      (node (ref "R23") (pin "2") (pinfunction "2_2") (pintype "passive"))
    )
    (net (code "21") (name "/U0RXD") (class "Default")
      (node (ref "IC2_ESP32S2WROOMM22S2") (pin "38") (pinfunction "RXD0_38") (pintype "bidirectional"))
      (node (ref "UART0") (pin "2") (pinfunction "2_2") (pintype "passive"))
    )
    (net (code "22") (name "/U0TXD") (class "Default")
      (node (ref "IC2_ESP32S2WROOMM22S2") (pin "37") (pinfunction "TXD0_37") (pintype "bidirectional"))
      (node (ref "UART0") (pin "1") (pinfunction "1_1") (pintype "passive"))
    )
    (net (code "23") (name "/U1RXD") (class "Default")
      (node (ref "IC2_ESP32S2WROOMM22S2") (pin "21") (pinfunction "IO18_21") (pintype "bidirectional"))
      (node (ref "UART1") (pin "2") (pinfunction "2_2") (pintype "passive"))
    )
    (net (code "24") (name "/U1TXD") (class "Default")
      (node (ref "IC2_ESP32S2WROOMM22S2") (pin "20") (pinfunction "IO17_20") (pintype "bidirectional"))
      (node (ref "UART1") (pin "1") (pinfunction "1_1") (pintype "passive"))
    )
    (net (code "25") (name "/USB_D+") (class "Default")
      (node (ref "FL1-USB_EMI") (pin "3") (pinfunction "3_3") (pintype "bidirectional"))
      (node (ref "IC2_ESP32S2WROOMM22S2") (pin "23") (pinfunction "IO20_23") (pintype "bidirectional"))
    )
    (net (code "26") (name "/USB_D-") (class "Default")
      (node (ref "FL1-USB_EMI") (pin "2") (pinfunction "2_2") (pintype "bidirectional"))
      (node (ref "IC2_ESP32S2WROOMM22S2") (pin "22") (pinfunction "IO19_22") (pintype "bidirectional"))
    )
    (net (code "27") (name "/VDD1") (class "Default")
      (node (ref "C72") (pin "1") (pinfunction "1_1") (pintype "passive"))
      (node (ref "R20") (pin "1") (pinfunction "1_1") (pintype "passive"))
      (node (ref "U7") (pin "5") (pinfunction "OUT_5") (pintype "output"))
    )
    (net (code "28") (name "/VDD1F") (class "Default")
      (node (ref "C1") (pin "1") (pinfunction "1_1") (pintype "passive"))
      (node (ref "C14") (pin "1") (pinfunction "1_1") (pintype "passive"))
      (node (ref "R20") (pin "2") (pinfunction "2_2") (pintype "passive"))
      (node (ref "U1") (pin "1") (pinfunction "VDD_IO_1") (pintype "power_in"))
      (node (ref "U1") (pin "10") (pinfunction "VDD_10") (pintype "power_in"))
      (node (ref "U1") (pin "5") (pinfunction "SDO/SA0_5") (pintype "bidirectional"))
      (node (ref "U1") (pin "6") (pinfunction "CS_6") (pintype "input"))
    )
    (net (code "29") (name "/VDD2") (class "Default")
      (node (ref "C62") (pin "1") (pinfunction "1_1") (pintype "passive"))
      (node (ref "R19") (pin "1") (pinfunction "1_1") (pintype "passive"))
      (node (ref "U6") (pin "5") (pinfunction "OUT_5") (pintype "output"))
    )
    (net (code "30") (name "/VDD2F") (class "Default")
      (node (ref "C15") (pin "1") (pinfunction "1_1") (pintype "passive"))
      (node (ref "C2") (pin "1") (pinfunction "1_1") (pintype "passive"))
      (node (ref "R19") (pin "2") (pinfunction "2_2") (pintype "passive"))
      (node (ref "U2") (pin "1") (pinfunction "VDD_IO_1") (pintype "power_in"))
      (node (ref "U2") (pin "10") (pinfunction "VDD_10") (pintype "power_in"))
      (node (ref "U2") (pin "6") (pinfunction "CS_6") (pintype "input"))
    )
    (net (code "31") (name "/VDD3") (class "Default")
      (node (ref "C52") (pin "1") (pinfunction "1_1") (pintype "passive"))
      (node (ref "R18") (pin "1") (pinfunction "1_1") (pintype "passive"))
      (node (ref "U5") (pin "5") (pinfunction "OUT_5") (pintype "output"))
    )
    (net (code "32") (name "/VDD3F") (class "Default")
      (node (ref "C11") (pin "1") (pinfunction "1_1") (pintype "passive"))
      (node (ref "R18") (pin "2") (pinfunction "2_2") (pintype "passive"))
      (node (ref "U3-IMU") (pin "12") (pinfunction "CS_12") (pintype "input"))
      (node (ref "U3-IMU") (pin "5") (pinfunction "VDDIO_5") (pintype "power_in"))
      (node (ref "U3-IMU") (pin "8") (pinfunction "VDD_8") (pintype "power_in"))
    )
    (net (code "33") (name "/VDD4") (class "Default")
      (node (ref "C42") (pin "1") (pinfunction "1_1") (pintype "passive"))
      (node (ref "R13") (pin "2") (pinfunction "2_2") (pintype "passive"))
      (node (ref "R21") (pin "1") (pinfunction "1_1") (pintype "passive"))
      (node (ref "U4") (pin "5") (pinfunction "OUT_5") (pintype "output"))
    )
    (net (code "34") (name "/VDD4F") (class "Default")
      (node (ref "C16") (pin "1") (pinfunction "1_1") (pintype "passive"))
      (node (ref "C3") (pin "1") (pinfunction "1_1") (pintype "passive"))
      (node (ref "DLHR-L30G-E1BD-C-NAV8") (pin "2-VS") (pinfunction "2-VS_2-VS") (pintype "power_in"))
      (node (ref "R21") (pin "2") (pinfunction "2_2") (pintype "passive"))
      (node (ref "U$1") (pin "2-VCC") (pinfunction "VCC_2-VCC") (pintype "bidirectional"))
      (node (ref "U$4") (pin "2-VS") (pinfunction "2-VS_2-VS") (pintype "power_in"))
    )
    (net (code "35") (name "/VDD5") (class "Default")
      (node (ref "C10") (pin "1") (pinfunction "1_1") (pintype "passive"))
      (node (ref "R22") (pin "1") (pinfunction "1_1") (pintype "passive"))
      (node (ref "U12") (pin "5") (pinfunction "OUT_5") (pintype "output"))
    )
    (net (code "36") (name "/VDD5F") (class "Default")
      (node (ref "C7") (pin "1") (pinfunction "1_1") (pintype "passive"))
      (node (ref "C9") (pin "1") (pinfunction "1_1") (pintype "passive"))
      (node (ref "R22") (pin "2") (pinfunction "2_2") (pintype "passive"))
      (node (ref "U10-MAG_SENSOR") (pin "13") (pinfunction "VDDIO_13") (pintype "power_in"))
      (node (ref "U10-MAG_SENSOR") (pin "2") (pinfunction "VDD_2") (pintype "power_in"))
      (node (ref "U10-MAG_SENSOR") (pin "4") (pinfunction "CS_4") (pintype "input"))
    )
    (net (code "37") (name "Net-(12V_INA-S)") (class "Default")
      (node (ref "12V_IN") (pin "1") (pinfunction "S_1") (pintype "passive"))
      (node (ref "F1") (pin "1") (pinfunction "1_1") (pintype "bidirectional"))
    )
    (net (code "38") (name "Net-(C20-Pad2)") (class "Default")
      (node (ref "C20") (pin "2") (pinfunction "2_2") (pintype "passive"))
      (node (ref "R11") (pin "2") (pinfunction "2_2") (pintype "passive"))
      (node (ref "R12") (pin "2") (pinfunction "2_2") (pintype "passive"))
      (node (ref "R9") (pin "1") (pinfunction "1_1") (pintype "passive"))
    )
    (net (code "39") (name "Net-(C21-Pad2)") (class "Default")
      (node (ref "C21") (pin "2") (pinfunction "2_2") (pintype "bidirectional"))
      (node (ref "D1") (pin "C") (pinfunction "C_C") (pintype "passive"))
      (node (ref "L1") (pin "1") (pinfunction "1_1") (pintype "bidirectional"))
    )
    (net (code "40") (name "Net-(C25-Pad2)") (class "Default")
      (node (ref "C25") (pin "2") (pinfunction "2_2") (pintype "passive"))
      (node (ref "R15") (pin "1") (pinfunction "1_1") (pintype "passive"))
    )
    (net (code "41") (name "Net-(C26-Pad2)") (class "Default")
      (node (ref "C26") (pin "2") (pinfunction "2_2") (pintype "passive"))
      (node (ref "R14") (pin "1") (pinfunction "1_1") (pintype "passive"))
    )
    (net (code "42") (name "Net-(D1-PadA)") (class "Default")
      (node (ref "D1") (pin "A") (pinfunction "A_A") (pintype "passive"))
      (node (ref "F1") (pin "2") (pinfunction "2_2") (pintype "bidirectional"))
    )
    (net (code "43") (name "Net-(D2-A)") (class "Default")
      (node (ref "C18") (pin "2") (pinfunction "2_2") (pintype "bidirectional"))
      (node (ref "C20") (pin "1") (pinfunction "1_1") (pintype "passive"))
      (node (ref "D2") (pin "2") (pinfunction "A_2") (pintype "bidirectional"))
      (node (ref "L2") (pin "2") (pinfunction "2_2") (pintype "bidirectional"))
      (node (ref "R9") (pin "2") (pinfunction "2_2") (pintype "passive"))
    )
    (net (code "44") (name "Net-(FL1-USB_EMI-Pad1)") (class "Default")
      (node (ref "FL1-USB_EMI") (pin "1") (pinfunction "1_1") (pintype "bidirectional"))
      (node (ref "R16") (pin "1") (pinfunction "1_1") (pintype "passive"))
    )
    (net (code "45") (name "Net-(FL1-USB_EMI-Pad4)") (class "Default")
      (node (ref "FL1-USB_EMI") (pin "4") (pinfunction "4_4") (pintype "bidirectional"))
      (node (ref "R17") (pin "1") (pinfunction "1_1") (pintype "passive"))
    )
    (net (code "46") (name "Net-(IC2_ESP32S2WROOMM22S2-EN)") (class "Default")
      (node (ref "IC2_ESP32S2WROOMM22S2") (pin "41") (pinfunction "EN_41") (pintype "bidirectional"))
      (node (ref "R10") (pin "1") (pinfunction "1_1") (pintype "passive"))
    )
    (net (code "47") (name "Net-(IC2_ESP32S2WROOMM22S2-IO46)") (class "Default")
      (node (ref "IC2_ESP32S2WROOMM22S2") (pin "40") (pinfunction "IO46_40") (pintype "bidirectional"))
      (node (ref "WIFI_EN") (pin "1") (pinfunction "1_1") (pintype "passive"))
    )
    (net (code "48") (name "Net-(IC4-BYPASS)") (class "Default")
      (node (ref "C27") (pin "1") (pinfunction "1_1") (pintype "passive"))
      (node (ref "IC4") (pin "2") (pinfunction "BYPASS_2") (pintype "bidirectional"))
    )
    (net (code "49") (name "Net-(IC4-IN+)") (class "Default")
      (node (ref "C24") (pin "1") (pinfunction "1_1") (pintype "passive"))
      (node (ref "IC4") (pin "3") (pinfunction "IN+_3") (pintype "bidirectional"))
      (node (ref "R14") (pin "2") (pinfunction "2_2") (pintype "passive"))
    )
    (net (code "50") (name "Net-(IC4-IN-)") (class "Default")
      (node (ref "C23") (pin "1") (pinfunction "1_1") (pintype "passive"))
      (node (ref "IC4") (pin "4") (pinfunction "IN-_4") (pintype "bidirectional"))
      (node (ref "R15") (pin "2") (pinfunction "2_2") (pintype "passive"))
    )
    (net (code "51") (name "Net-(J4_USB-Pad2)") (class "Default")
      (node (ref "J4_USB") (pin "2") (pinfunction "2_2") (pintype "bidirectional"))
      (node (ref "R16") (pin "2") (pinfunction "2_2") (pintype "passive"))
    )
    (net (code "52") (name "Net-(J4_USB-Pad3)") (class "Default")
      (node (ref "J4_USB") (pin "3") (pinfunction "3_3") (pintype "bidirectional"))
      (node (ref "R17") (pin "2") (pinfunction "2_2") (pintype "passive"))
    )
    (net (code "53") (name "Net-(PS1-BST)") (class "Default")
      (node (ref "C19") (pin "2") (pinfunction "2_2") (pintype "passive"))
      (node (ref "PS1") (pin "6") (pinfunction "BST_6") (pintype "input"))
    )
    (net (code "54") (name "Net-(PS1-EN)") (class "Default")
      (node (ref "C17") (pin "2") (pinfunction "2_2") (pintype "bidirectional"))
      (node (ref "L1") (pin "2") (pinfunction "2_2") (pintype "bidirectional"))
      (node (ref "PS1") (pin "3") (pinfunction "IN_3") (pintype "input"))
      (node (ref "PS1") (pin "5") (pinfunction "EN_5") (pintype "input"))
    )
    (net (code "55") (name "Net-(PS1-FB)") (class "Default")
      (node (ref "PS1") (pin "4") (pinfunction "FB_4") (pintype "input"))
      (node (ref "R12") (pin "1") (pinfunction "1_1") (pintype "passive"))
    )
    (net (code "56") (name "Net-(PS1-SW)") (class "Default")
      (node (ref "C19") (pin "1") (pinfunction "1_1") (pintype "passive"))
      (node (ref "L2") (pin "1") (pinfunction "1_1") (pintype "bidirectional"))
      (node (ref "PS1") (pin "2") (pinfunction "SW_2") (pintype "output"))
    )
    (net (code "57") (name "Net-(U4-EN)") (class "Default")
      (node (ref "C41") (pin "1") (pinfunction "1_1") (pintype "passive"))
      (node (ref "R6") (pin "2") (pinfunction "2_2") (pintype "passive"))
      (node (ref "U4") (pin "1") (pinfunction "IN_1") (pintype "input"))
      (node (ref "U4") (pin "3") (pinfunction "EN_3") (pintype "input"))
    )
    (net (code "58") (name "Net-(U5-EN)") (class "Default")
      (node (ref "C51") (pin "1") (pinfunction "1_1") (pintype "passive"))
      (node (ref "R5") (pin "2") (pinfunction "2_2") (pintype "passive"))
      (node (ref "U5") (pin "1") (pinfunction "IN_1") (pintype "input"))
      (node (ref "U5") (pin "3") (pinfunction "EN_3") (pintype "input"))
    )
    (net (code "59") (name "Net-(U6-EN)") (class "Default")
      (node (ref "C61") (pin "1") (pinfunction "1_1") (pintype "passive"))
      (node (ref "R4") (pin "2") (pinfunction "2_2") (pintype "passive"))
      (node (ref "U6") (pin "1") (pinfunction "IN_1") (pintype "input"))
      (node (ref "U6") (pin "3") (pinfunction "EN_3") (pintype "input"))
    )
    (net (code "60") (name "Net-(U7-EN)") (class "Default")
      (node (ref "C71") (pin "1") (pinfunction "1_1") (pintype "passive"))
      (node (ref "R3") (pin "2") (pinfunction "2_2") (pintype "passive"))
      (node (ref "U7") (pin "1") (pinfunction "IN_1") (pintype "input"))
      (node (ref "U7") (pin "3") (pinfunction "EN_3") (pintype "input"))
    )
    (net (code "61") (name "Net-(U10-MAG_SENSOR-CAP)") (class "Default")
      (node (ref "C8") (pin "1") (pinfunction "1_1") (pintype "passive"))
      (node (ref "U10-MAG_SENSOR") (pin "10") (pinfunction "CAP_10") (pintype "power_in"))
    )
    (net (code "62") (name "Net-(U11-EN)") (class "Default")
      (node (ref "C5") (pin "1") (pinfunction "1_1") (pintype "passive"))
      (node (ref "R8") (pin "2") (pinfunction "2_2") (pintype "passive"))
      (node (ref "U11") (pin "4") (pinfunction "VIN_4") (pintype "input"))
      (node (ref "U11") (pin "6") (pinfunction "EN_6") (pintype "input"))
    )
    (net (code "63") (name "Net-(U12-EN)") (class "Default")
      (node (ref "C12") (pin "1") (pinfunction "1_1") (pintype "passive"))
      (node (ref "R7") (pin "2") (pinfunction "2_2") (pintype "passive"))
      (node (ref "U12") (pin "1") (pinfunction "IN_1") (pintype "input"))
      (node (ref "U12") (pin "3") (pinfunction "EN_3") (pintype "input"))
    )
    (net (code "64") (name "unconnected-(DLHR-L30G-E1BD-C-NAV8-8-{slash}SS-Pad8-SS)") (class "Default")
      (node (ref "DLHR-L30G-E1BD-C-NAV8") (pin "8-SS") (pinfunction "8-/SS_8-SS") (pintype "bidirectional"))
    )
    (net (code "65") (name "unconnected-(DLHR-L30G-E1BD-C-NAV8-Pad5-EOC)") (class "Default")
      (node (ref "DLHR-L30G-E1BD-C-NAV8") (pin "5-EOC") (pinfunction "5-EOC_5-EOC") (pintype "bidirectional"))
    )
    (net (code "66") (name "unconnected-(DLHR-L30G-E1BD-C-NAV8-Pad6-MISO)") (class "Default")
      (node (ref "DLHR-L30G-E1BD-C-NAV8") (pin "6-MISO") (pinfunction "6-MISO_6-MISO") (pintype "bidirectional"))
    )
    (net (code "67") (name "unconnected-(DLHR-L30G-E1BD-C-NAV8-Pad7-NC)") (class "Default")
      (node (ref "DLHR-L30G-E1BD-C-NAV8") (pin "7-NC") (pinfunction "7-NC_7-NC") (pintype "bidirectional"))
    )
    (net (code "68") (name "unconnected-(IC2_ESP32S2WROOMM22S2-IO0-Pad3)") (class "Default")
      (node (ref "IC2_ESP32S2WROOMM22S2") (pin "3") (pinfunction "IO0_3") (pintype "bidirectional"))
    )
    (net (code "69") (name "unconnected-(IC2_ESP32S2WROOMM22S2-IO1-Pad4)") (class "Default")
      (node (ref "IC2_ESP32S2WROOMM22S2") (pin "4") (pinfunction "IO1_4") (pintype "bidirectional"))
    )
    (net (code "70") (name "unconnected-(IC2_ESP32S2WROOMM22S2-IO2-Pad5)") (class "Default")
      (node (ref "IC2_ESP32S2WROOMM22S2") (pin "5") (pinfunction "IO2_5") (pintype "bidirectional"))
    )
    (net (code "71") (name "unconnected-(IC2_ESP32S2WROOMM22S2-IO3-Pad6)") (class "Default")
      (node (ref "IC2_ESP32S2WROOMM22S2") (pin "6") (pinfunction "IO3_6") (pintype "bidirectional"))
    )
    (net (code "72") (name "unconnected-(IC2_ESP32S2WROOMM22S2-IO4-Pad7)") (class "Default")
      (node (ref "IC2_ESP32S2WROOMM22S2") (pin "7") (pinfunction "IO4_7") (pintype "bidirectional"))
    )
    (net (code "73") (name "unconnected-(IC2_ESP32S2WROOMM22S2-IO5-Pad8)") (class "Default")
      (node (ref "IC2_ESP32S2WROOMM22S2") (pin "8") (pinfunction "IO5_8") (pintype "bidirectional"))
    )
    (net (code "74") (name "unconnected-(IC2_ESP32S2WROOMM22S2-IO6-Pad9)") (class "Default")
      (node (ref "IC2_ESP32S2WROOMM22S2") (pin "9") (pinfunction "IO6_9") (pintype "bidirectional"))
    )
    (net (code "75") (name "unconnected-(IC2_ESP32S2WROOMM22S2-IO7-Pad10)") (class "Default")
      (node (ref "IC2_ESP32S2WROOMM22S2") (pin "10") (pinfunction "IO7_10") (pintype "bidirectional"))
    )
    (net (code "76") (name "unconnected-(IC2_ESP32S2WROOMM22S2-IO8-Pad11)") (class "Default")
      (node (ref "IC2_ESP32S2WROOMM22S2") (pin "11") (pinfunction "IO8_11") (pintype "bidirectional"))
    )
    (net (code "77") (name "unconnected-(IC2_ESP32S2WROOMM22S2-IO9-Pad12)") (class "Default")
      (node (ref "IC2_ESP32S2WROOMM22S2") (pin "12") (pinfunction "IO9_12") (pintype "bidirectional"))
    )
    (net (code "78") (name "unconnected-(IC2_ESP32S2WROOMM22S2-IO10-Pad13)") (class "Default")
      (node (ref "IC2_ESP32S2WROOMM22S2") (pin "13") (pinfunction "IO10_13") (pintype "bidirectional"))
    )
    (net (code "79") (name "unconnected-(IC2_ESP32S2WROOMM22S2-IO11-Pad14)") (class "Default")
      (node (ref "IC2_ESP32S2WROOMM22S2") (pin "14") (pinfunction "IO11_14") (pintype "bidirectional"))
    )
    (net (code "80") (name "unconnected-(IC2_ESP32S2WROOMM22S2-IO12-Pad15)") (class "Default")
      (node (ref "IC2_ESP32S2WROOMM22S2") (pin "15") (pinfunction "IO12_15") (pintype "bidirectional"))
    )
    (net (code "81") (name "unconnected-(IC2_ESP32S2WROOMM22S2-IO21-Pad24)") (class "Default")
      (node (ref "IC2_ESP32S2WROOMM22S2") (pin "24") (pinfunction "IO21_24") (pintype "bidirectional"))
    )
    (net (code "82") (name "unconnected-(IC2_ESP32S2WROOMM22S2-IO26-Pad25)") (class "Default")
      (node (ref "IC2_ESP32S2WROOMM22S2") (pin "25") (pinfunction "IO26_25") (pintype "bidirectional"))
    )
    (net (code "83") (name "unconnected-(IC2_ESP32S2WROOMM22S2-IO33-Pad27)") (class "Default")
      (node (ref "IC2_ESP32S2WROOMM22S2") (pin "27") (pinfunction "IO33_27") (pintype "bidirectional"))
    )
    (net (code "84") (name "unconnected-(IC2_ESP32S2WROOMM22S2-IO34-Pad28)") (class "Default")
      (node (ref "IC2_ESP32S2WROOMM22S2") (pin "28") (pinfunction "IO34_28") (pintype "bidirectional"))
    )
    (net (code "85") (name "unconnected-(IC2_ESP32S2WROOMM22S2-IO35-Pad29)") (class "Default")
      (node (ref "IC2_ESP32S2WROOMM22S2") (pin "29") (pinfunction "IO35_29") (pintype "bidirectional"))
    )
    (net (code "86") (name "unconnected-(IC2_ESP32S2WROOMM22S2-IO36-Pad30)") (class "Default")
      (node (ref "IC2_ESP32S2WROOMM22S2") (pin "30") (pinfunction "IO36_30") (pintype "bidirectional"))
    )
    (net (code "87") (name "unconnected-(IC2_ESP32S2WROOMM22S2-IO37-Pad31)") (class "Default")
      (node (ref "IC2_ESP32S2WROOMM22S2") (pin "31") (pinfunction "IO37_31") (pintype "bidirectional"))
    )
    (net (code "88") (name "unconnected-(IC2_ESP32S2WROOMM22S2-IO38-Pad32)") (class "Default")
      (node (ref "IC2_ESP32S2WROOMM22S2") (pin "32") (pinfunction "IO38_32") (pintype "bidirectional"))
    )
    (net (code "89") (name "unconnected-(IC2_ESP32S2WROOMM22S2-IO39-Pad33)") (class "Default")
      (node (ref "IC2_ESP32S2WROOMM22S2") (pin "33") (pinfunction "IO39_33") (pintype "bidirectional"))
    )
    (net (code "90") (name "unconnected-(IC2_ESP32S2WROOMM22S2-IO40-Pad34)") (class "Default")
      (node (ref "IC2_ESP32S2WROOMM22S2") (pin "34") (pinfunction "IO40_34") (pintype "bidirectional"))
    )
    (net (code "91") (name "unconnected-(IC2_ESP32S2WROOMM22S2-IO41-Pad35)") (class "Default")
      (node (ref "IC2_ESP32S2WROOMM22S2") (pin "35") (pinfunction "IO41_35") (pintype "bidirectional"))
    )
    (net (code "92") (name "unconnected-(IC2_ESP32S2WROOMM22S2-IO42-Pad36)") (class "Default")
      (node (ref "IC2_ESP32S2WROOMM22S2") (pin "36") (pinfunction "IO42_36") (pintype "bidirectional"))
    )
    (net (code "93") (name "unconnected-(J6_OAT-Pad4)") (class "Default")
      (node (ref "J6_OAT") (pin "4") (pinfunction "4_4") (pintype "bidirectional"))
    )
    (net (code "94") (name "unconnected-(U$4-Pad5-INT{slash}SS)") (class "Default")
      (node (ref "U$4") (pin "5-INT/SS") (pinfunction "5-INT/SS_5-INT/SS") (pintype "bidirectional"))
    )
    (net (code "95") (name "unconnected-(U$4-Pad6-NC)") (class "Default")
      (node (ref "U$4") (pin "6-NC") (pinfunction "6-NC_6-NC") (pintype "bidirectional"))
    )
    (net (code "96") (name "unconnected-(U$4-Pad7-NC)") (class "Default")
      (node (ref "U$4") (pin "7-NC") (pinfunction "7-NC_7-NC") (pintype "bidirectional"))
    )
    (net (code "97") (name "unconnected-(U$4-Pad8-NC)") (class "Default")
      (node (ref "U$4") (pin "8-NC") (pinfunction "8-NC_8-NC") (pintype "bidirectional"))
    )
    (net (code "98") (name "unconnected-(U1-INT_DRDY-Pad7)") (class "Default")
      (node (ref "U1") (pin "7") (pinfunction "INT_DRDY_7") (pintype "output"))
    )
    (net (code "99") (name "unconnected-(U2-INT_DRDY-Pad7)") (class "Default")
      (node (ref "U2") (pin "7") (pinfunction "INT_DRDY_7") (pintype "output"))
    )
    (net (code "100") (name "unconnected-(U3-IMU-INT1-Pad4)") (class "Default")
      (node (ref "U3-IMU") (pin "4") (pinfunction "INT1_4") (pintype "input"))
    )
    (net (code "101") (name "unconnected-(U3-IMU-INT2{slash}DEN{slash}MDRDY-Pad9)") (class "Default")
      (node (ref "U3-IMU") (pin "9") (pinfunction "INT2/DEN/MDRDY_9") (pintype "input"))
    )
    (net (code "102") (name "unconnected-(U3-IMU-OCS_AUX-Pad10)") (class "Default")
      (node (ref "U3-IMU") (pin "10") (pinfunction "OCS_AUX_10") (pintype "input"))
    )
    (net (code "103") (name "unconnected-(U3-IMU-SCX-Pad3)") (class "Default")
      (node (ref "U3-IMU") (pin "3") (pinfunction "SCX_3") (pintype "bidirectional"))
    )
    (net (code "104") (name "unconnected-(U3-IMU-SDO_AUX-Pad11)") (class "Default")
      (node (ref "U3-IMU") (pin "11") (pinfunction "SDO_AUX_11") (pintype "bidirectional"))
    )
    (net (code "105") (name "unconnected-(U3-IMU-SDO{slash}SA0-Pad1)") (class "Default")
      (node (ref "U3-IMU") (pin "1") (pinfunction "SDO/SA0_1") (pintype "bidirectional"))
    )
    (net (code "106") (name "unconnected-(U3-IMU-SDX-Pad2)") (class "Default")
      (node (ref "U3-IMU") (pin "2") (pinfunction "SDX_2") (pintype "bidirectional"))
    )
    (net (code "107") (name "unconnected-(U10-MAG_SENSOR-INT-Pad15)") (class "Default")
      (node (ref "U10-MAG_SENSOR") (pin "15") (pinfunction "INT_15") (pintype "output"))
    )
    (net (code "108") (name "unconnected-(U10-MAG_SENSOR-SDO-Pad5)") (class "Default")
      (node (ref "U10-MAG_SENSOR") (pin "5") (pinfunction "SDO_5") (pintype "bidirectional"))
    )
    (net (code "109") (name "unconnected-(U13-I2C-PCTLZ-Pad6)") (class "Default")
      (node (ref "U13-I2C") (pin "6") (pinfunction "PCTLZ_6") (pintype "output"))
    )
  )
)
